# ASBB_MAX98357.net
KiCad netlist of a schematic drawn in Altium Designer
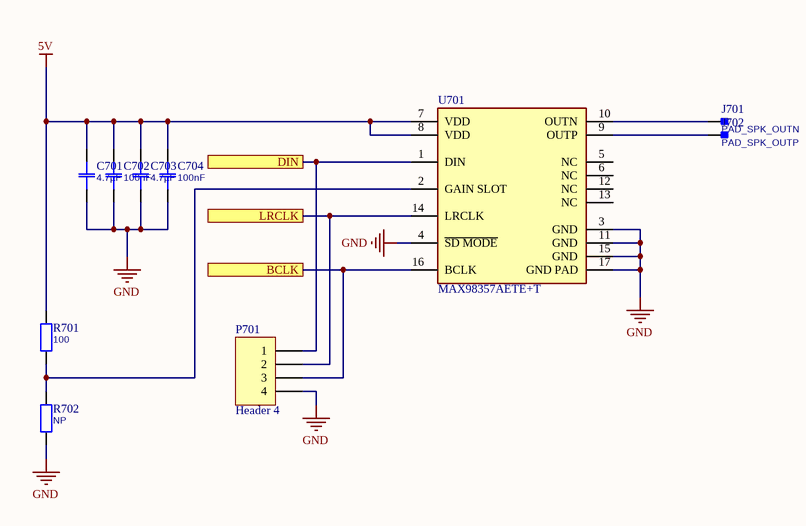
[diagram p0: ASBB_MAX98357.SchDoc]

(export (version "E")
  (design (tool "Eeschema 10.0.6"))
  (components
    (comp (ref "C701")
      (value "4.7µF")
      (footprint "0603")
      (description "Capacitor")
      (fields (field (name "PARTNUMBER") "?"))
      (libsource (lib "FZI") (part "Capacitor"))
    )
    (comp (ref "C702")
      (value "100nF")
      (footprint "0603")
      (description "Capacitor")
      (fields (field (name "PARTNUMBER") "?"))
      (libsource (lib "FZI") (part "Capacitor"))
    )
    (comp (ref "C703")
      (value "4.7µF")
      (footprint "0603")
      (description "Capacitor")
      (fields (field (name "PARTNUMBER") "?"))
      (libsource (lib "FZI") (part "Capacitor"))
    )
    (comp (ref "C704")
      (value "100nF")
      (footprint "0603")
      (description "Capacitor")
      (fields (field (name "PARTNUMBER") "?"))
      (libsource (lib "FZI") (part "Capacitor"))
    )
    (comp (ref "J701")
      (value "PAD_SPK_OUTN")
      (footprint "PIN1")
      (description "Pad, 1 Pin")
      (libsource (lib "FZI") (part "Pad 1 Pin"))
    )
    (comp (ref "J702")
      (value "PAD_SPK_OUTP")
      (footprint "PIN1")
      (description "Pad, 1 Pin")
      (libsource (lib "FZI") (part "Pad 1 Pin"))
    )
    (comp (ref "P701")
      (value "Header 4")
      (footprint "HDR1X4")
      (description "Header, 4-Pin")
      (fields (field (name "PUBLISHER") "Altium Limited"))
      (libsource (lib "Miscellaneous Connectors") (part "Header 4"))
    )
    (comp (ref "R701")
      (value "100")
      (footprint "0603")
      (description "Resistor")
      (fields (field (name "PARTNUMBER") "?"))
      (libsource (lib "FZI") (part "Resistor"))
    )
    (comp (ref "R702")
      (value "NP")
      (footprint "0603")
      (description "Resistor")
      (fields (field (name "PARTNUMBER") "?"))
      (libsource (lib "FZI") (part "Resistor"))
    )
    (comp (ref "U701")
      (value "IC_Maxim_Electronics_MAX98357AETE+T_eec")
      (footprint "IC_Maxim_Electronics_MAX98357AETE+T_eec_0:Maxim_Electronics_21-0896_0")
      (description "IC Amplifier IC 2-Channel (Stereo) Class D 16-TQFN (3x3)")
      (fields
        (field (name "MANUFACTURER") "Maxim Electronics")
        (field (name "MOUSER PART NUMBER") "700-MAX98357AETE+T")
        (field (name "PART NUMBER") "MAX98357AETE+T")
      )
      (libsource (lib "IC_Maxim_Electronics_MAX98357AETE+T_eec") (part "IC_Maxim_Electronics_MAX98357AETE+T_eec"))
    )
  )
  (nets
    (net (code "1") (name "/BCLK") (class "Default")
      (node (ref "P701") (pin "3") (pinfunction "3_3") (pintype "passive"))
      (node (ref "U701") (pin "16") (pinfunction "BCLK_16") (pintype "passive"))
    )
    (net (code "2") (name "/DIN") (class "Default")
      (node (ref "P701") (pin "1") (pinfunction "1_1") (pintype "passive"))
      (node (ref "U701") (pin "1") (pinfunction "DIN_1") (pintype "passive"))
    )
    (net (code "3") (name "/LRCLK") (class "Default")
      (node (ref "P701") (pin "2") (pinfunction "2_2") (pintype "passive"))
      (node (ref "U701") (pin "14") (pinfunction "LRCLK_14") (pintype "passive"))
    )
    (net (code "4") (name "5V") (class "Default")
      (node (ref "C701") (pin "2") (pinfunction "2_2") (pintype "passive"))
      (node (ref "C702") (pin "2") (pinfunction "2_2") (pintype "passive"))
      (node (ref "C703") (pin "2") (pinfunction "2_2") (pintype "passive"))
      (node (ref "C704") (pin "2") (pinfunction "2_2") (pintype "passive"))
      (node (ref "R701") (pin "2") (pinfunction "2_2") (pintype "passive"))
      (node (ref "U701") (pin "7") (pinfunction "VDD_7") (pintype "passive"))
      (node (ref "U701") (pin "8") (pinfunction "VDD_8") (pintype "passive"))
    )
    (net (code "5") (name "GND") (class "Default")
      (node (ref "C701") (pin "1") (pinfunction "1_1") (pintype "passive"))
      (node (ref "C702") (pin "1") (pinfunction "1_1") (pintype "passive"))
      (node (ref "C703") (pin "1") (pinfunction "1_1") (pintype "passive"))
      (node (ref "C704") (pin "1") (pinfunction "1_1") (pintype "passive"))
      (node (ref "P701") (pin "4") (pinfunction "4_4") (pintype "passive"))
      (node (ref "R702") (pin "1") (pinfunction "1_1") (pintype "passive"))
      (node (ref "U701") (pin "11") (pinfunction "GND_11") (pintype "passive"))
      (node (ref "U701") (pin "15") (pinfunction "GND_15") (pintype "passive"))
      (node (ref "U701") (pin "17") (pinfunction "GND_PAD_17") (pintype "passive"))
      (node (ref "U701") (pin "3") (pinfunction "GND_3") (pintype "passive"))
      (node (ref "U701") (pin "4") (pinfunction "~{SD_MODE}_4") (pintype "passive"))
    )
    (net (code "6") (name "Net-(U701-GAIN_SLOT)") (class "Default")
      (node (ref "R701") (pin "1") (pinfunction "1_1") (pintype "passive"))
      (node (ref "R702") (pin "2") (pinfunction "2_2") (pintype "passive"))
      (node (ref "U701") (pin "2") (pinfunction "GAIN_SLOT_2") (pintype "passive"))
    )
    (net (code "7") (name "Net-(U701-OUTN)") (class "Default")
      (node (ref "J701") (pin "1") (pinfunction "1_1") (pintype "passive"))
      (node (ref "U701") (pin "10") (pinfunction "OUTN_10") (pintype "passive"))
    )
    (net (code "8") (name "Net-(U701-OUTP)") (class "Default")
      (node (ref "J702") (pin "1") (pinfunction "1_1") (pintype "passive"))
      (node (ref "U701") (pin "9") (pinfunction "OUTP_9") (pintype "passive"))
    )
    (net (code "9") (name "unconnected-(U701-NC-Pad5)") (class "Default")
      (node (ref "U701") (pin "5") (pinfunction "NC_5") (pintype "passive"))
    )
    (net (code "10") (name "unconnected-(U701-NC-Pad6)") (class "Default")
      (node (ref "U701") (pin "6") (pinfunction "NC_6") (pintype "passive"))
    )
    (net (code "11") (name "unconnected-(U701-NC-Pad12)") (class "Default")
      (node (ref "U701") (pin "12") (pinfunction "NC_12") (pintype "passive"))
    )
    (net (code "12") (name "unconnected-(U701-NC-Pad13)") (class "Default")
      (node (ref "U701") (pin "13") (pinfunction "NC_13") (pintype "passive"))
    )
  )
)
